# eurorack-passive-jfet.net
KiCad netlist of a schematic drawn in EAGLE
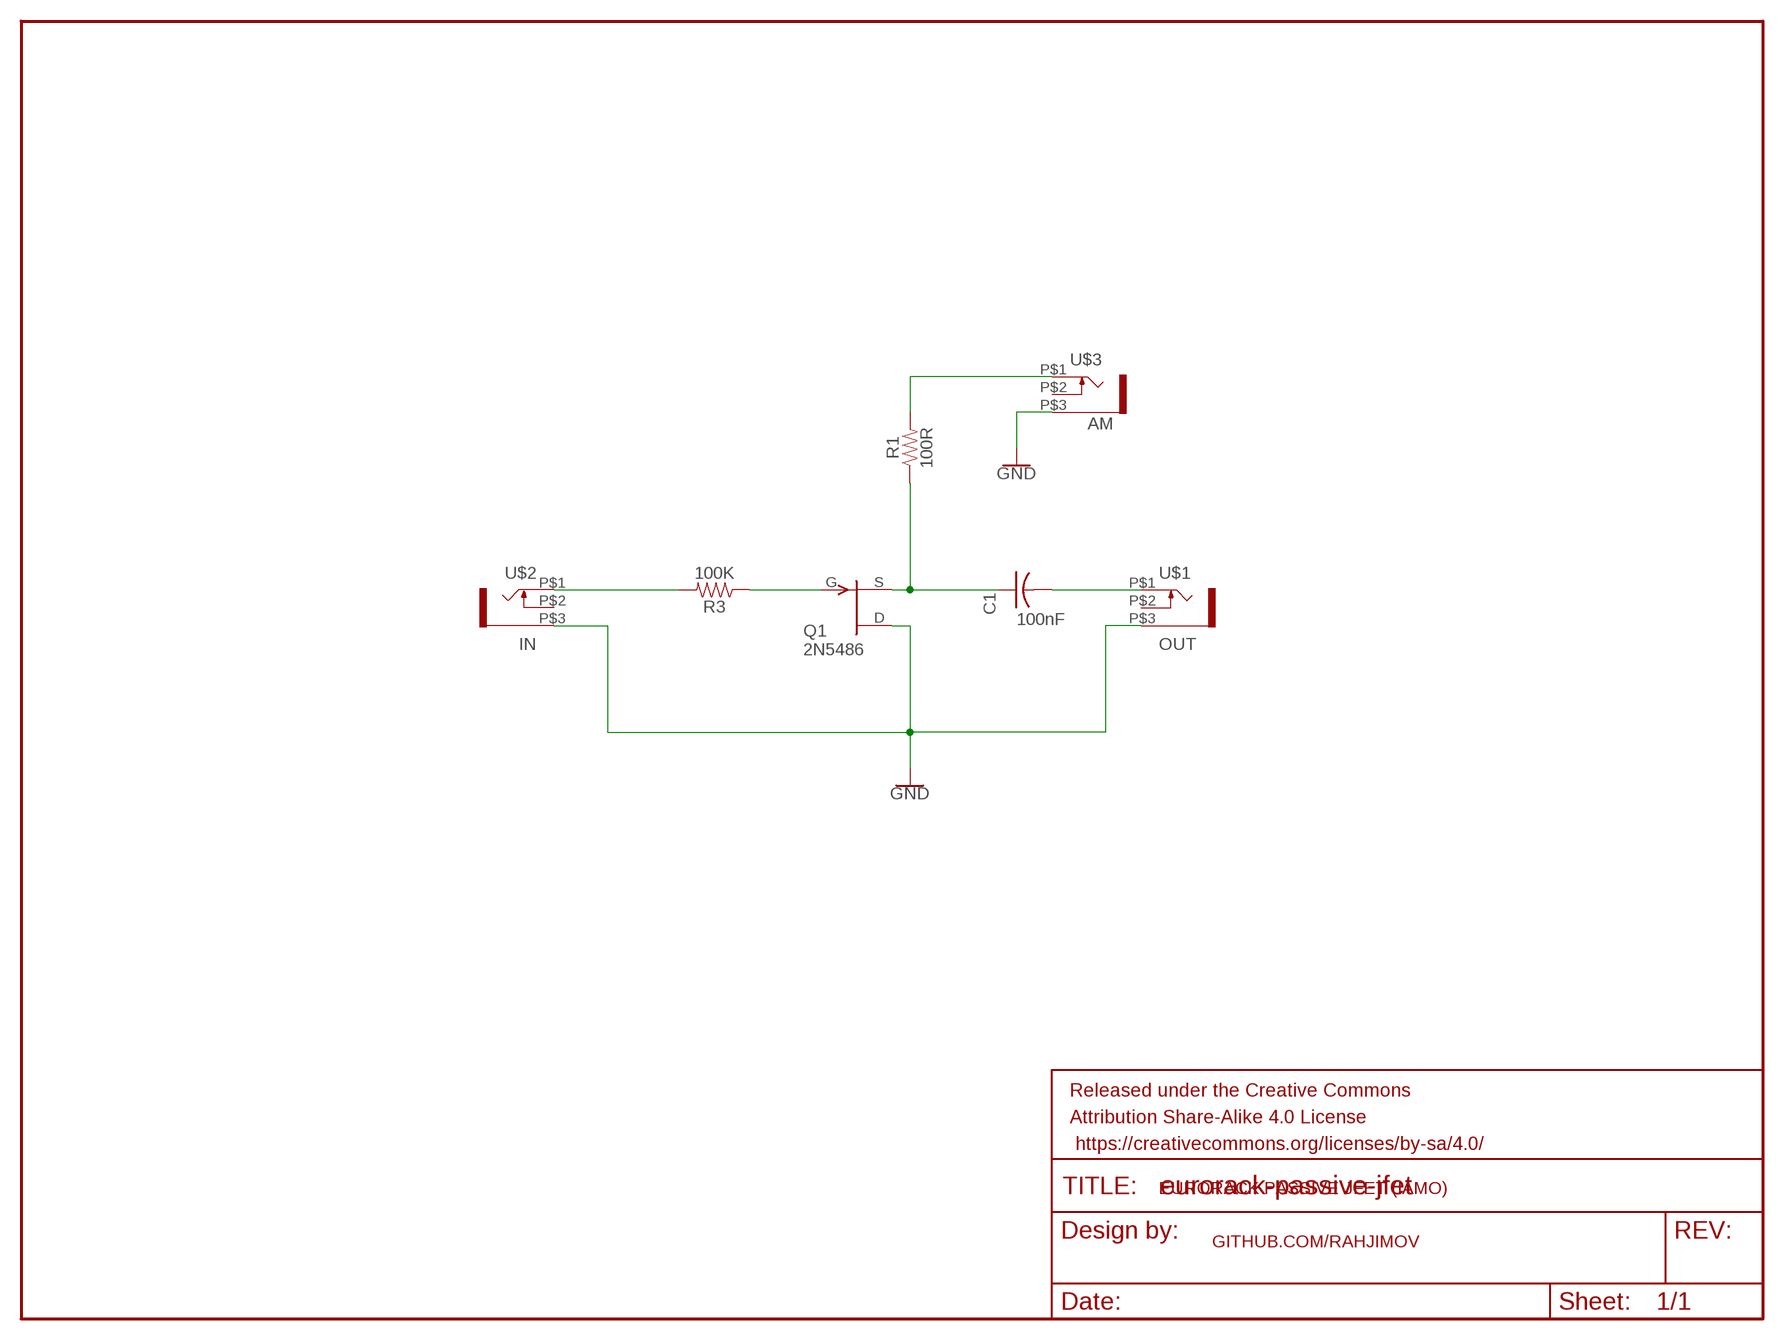
[diagram p0: schematic, sheet 1]

(export (version "E")
  (design (tool "Eeschema 10.0.6"))
  (components
    (comp (ref "C1")
      (value "100nF")
      (footprint "eagle-import:C025-025X050")
      (libsource (lib "eagle-import") (part "C-US025-025X050"))
    )
    (comp (ref "FRAME1")
      (value "FRAME-LETTERNO_PACKAGE")
      (footprint "eagle-import:DUMMY")
      (fields (field (name "DESIGNER") "Nobody"))
      (libsource (lib "eagle-import") (part "FRAME-LETTERNO_PACKAGE"))
    )
    (comp (ref "Q1")
      (value "2N5486")
      (footprint "eagle-import:TO92-")
      (libsource (lib "eagle-import") (part "?5482N6"))
    )
    (comp (ref "R1")
      (value "100R")
      (footprint "eagle-import:AXIAL-0.3")
      (libsource (lib "eagle-import") (part "330OHM-HORIZ-1/10W-5%"))
    )
    (comp (ref "R3")
      (value "100K")
      (footprint "eagle-import:AXIAL-0.3")
      (libsource (lib "eagle-import") (part "330OHM-HORIZ-1/10W-5%"))
    )
    (comp (ref "U$1")
      (value "OUT")
      (footprint "eagle-import:WQP-PJ301M-12_JACK")
      (libsource (lib "eagle-import") (part "WQP-PJ301M-12_JACK"))
    )
    (comp (ref "U$2")
      (value "IN")
      (footprint "eagle-import:WQP-PJ301M-12_JACK")
      (libsource (lib "eagle-import") (part "WQP-PJ301M-12_JACK"))
    )
    (comp (ref "U$3")
      (value "OUT")
      (footprint "eagle-import:WQP-PJ301M-12_JACK")
      (libsource (lib "eagle-import") (part "WQP-PJ301M-12_JACK"))
    )
  )
  (nets
    (net (code "1") (name "GND") (class "Default")
      (node (ref "Q1") (pin "3") (pinfunction "D_3") (pintype "passive"))
      (node (ref "U$1") (pin "P$3") (pinfunction "1_P$3") (pintype "passive"))
      (node (ref "U$2") (pin "P$3") (pinfunction "1_P$3") (pintype "passive"))
      (node (ref "U$3") (pin "P$3") (pinfunction "1_P$3") (pintype "passive"))
    )
    (net (code "2") (name "Net-(Q1-G)") (class "Default")
      (node (ref "Q1") (pin "1") (pinfunction "G_1") (pintype "passive"))
      (node (ref "R3") (pin "P$1") (pinfunction "1_P$1") (pintype "passive"))
    )
    (net (code "3") (name "Net-(Q1-S)") (class "Default")
      (node (ref "C1") (pin "1") (pinfunction "1_1") (pintype "passive"))
      (node (ref "Q1") (pin "2") (pinfunction "S_2") (pintype "passive"))
      (node (ref "R1") (pin "P$1") (pinfunction "1_P$1") (pintype "passive"))
    )
    (net (code "4") (name "Net-(R1-2)") (class "Default")
      (node (ref "R1") (pin "P$2") (pinfunction "2_P$2") (pintype "passive"))
      (node (ref "U$3") (pin "P$1") (pinfunction "2_P$1") (pintype "passive"))
    )
    (net (code "5") (name "Net-(R3-2)") (class "Default")
      (node (ref "R3") (pin "P$2") (pinfunction "2_P$2") (pintype "passive"))
      (node (ref "U$2") (pin "P$1") (pinfunction "2_P$1") (pintype "passive"))
    )
    (net (code "6") (name "Net-(U$1-2)") (class "Default")
      (node (ref "C1") (pin "2") (pinfunction "2_2") (pintype "passive"))
      (node (ref "U$1") (pin "P$1") (pinfunction "2_P$1") (pintype "passive"))
    )
    (net (code "7") (name "unconnected-(U$1-3-PadP$2)") (class "Default")
      (node (ref "U$1") (pin "P$2") (pinfunction "3_P$2") (pintype "passive"))
    )
    (net (code "8") (name "unconnected-(U$2-3-PadP$2)") (class "Default")
      (node (ref "U$2") (pin "P$2") (pinfunction "3_P$2") (pintype "passive"))
    )
    (net (code "9") (name "unconnected-(U$3-3-PadP$2)") (class "Default")
      (node (ref "U$3") (pin "P$2") (pinfunction "3_P$2") (pintype "passive"))
    )
  )
)
